# aircopter.net
KiCad netlist of a schematic drawn in EAGLE
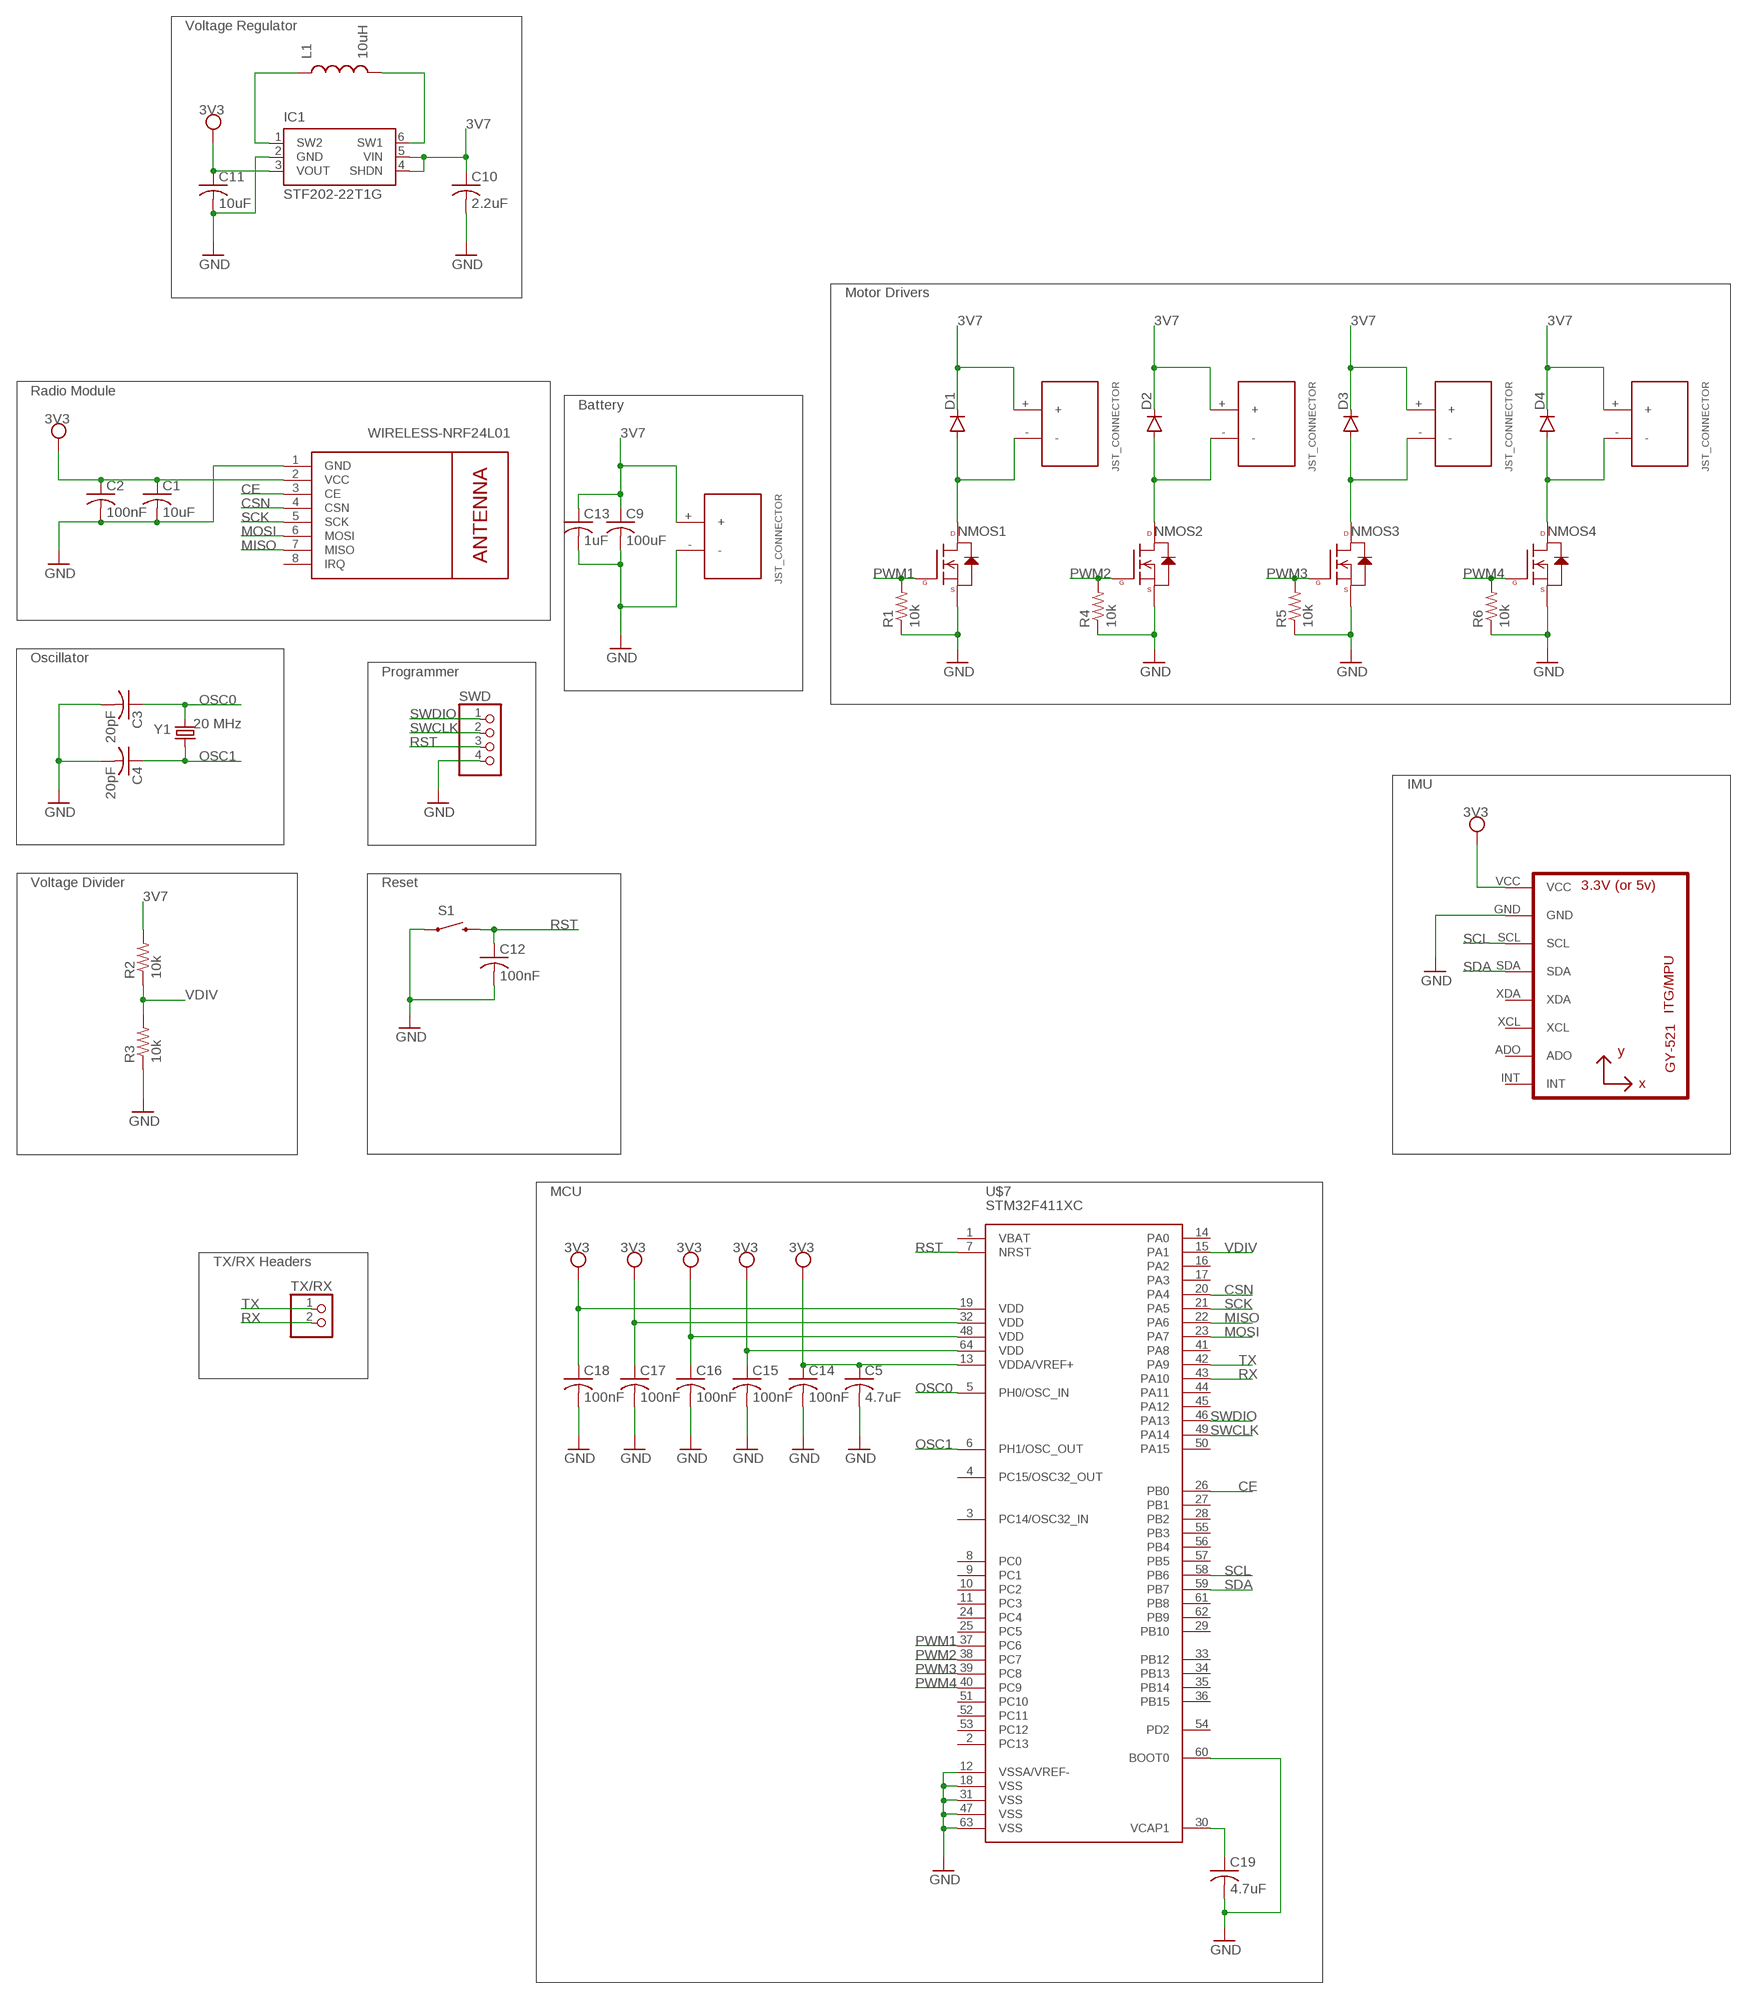
[diagram p0: schematic, sheet 1]

(export (version "E")
  (design (tool "Eeschema 10.0.6"))
  (components
    (comp (ref "C1")
      (value "10uF")
      (footprint "eagle-import:C0603")
      (libsource (lib "eagle-import") (part "C-USC0603"))
    )
    (comp (ref "C2")
      (value "100nF")
      (footprint "eagle-import:C0603")
      (libsource (lib "eagle-import") (part "C-USC0603"))
    )
    (comp (ref "C3")
      (value "20pF")
      (footprint "eagle-import:C0603")
      (libsource (lib "eagle-import") (part "C-USC0603"))
    )
    (comp (ref "C4")
      (value "20pF")
      (footprint "eagle-import:C0603")
      (libsource (lib "eagle-import") (part "C-USC0603"))
    )
    (comp (ref "C5")
      (value "4.7uF")
      (footprint "eagle-import:C0603")
      (libsource (lib "eagle-import") (part "C-USC0603"))
    )
    (comp (ref "C9")
      (value "100uF")
      (footprint "eagle-import:C0603")
      (libsource (lib "eagle-import") (part "C-USC0603"))
    )
    (comp (ref "C10")
      (value "2.2uF")
      (footprint "eagle-import:C0603")
      (libsource (lib "eagle-import") (part "C-USC0603"))
    )
    (comp (ref "C11")
      (value "10uF")
      (footprint "eagle-import:C0603")
      (libsource (lib "eagle-import") (part "C-USC0603"))
    )
    (comp (ref "C12")
      (value "100nF")
      (footprint "eagle-import:C0603")
      (libsource (lib "eagle-import") (part "C-USC0603"))
    )
    (comp (ref "C13")
      (value "1uF")
      (footprint "eagle-import:C0603")
      (libsource (lib "eagle-import") (part "C-USC0603"))
    )
    (comp (ref "C14")
      (value "100nF")
      (footprint "eagle-import:C0603")
      (libsource (lib "eagle-import") (part "C-USC0603"))
    )
    (comp (ref "C15")
      (value "100nF")
      (footprint "eagle-import:C0603")
      (libsource (lib "eagle-import") (part "C-USC0603"))
    )
    (comp (ref "C16")
      (value "100nF")
      (footprint "eagle-import:C0603")
      (libsource (lib "eagle-import") (part "C-USC0603"))
    )
    (comp (ref "C17")
      (value "100nF")
      (footprint "eagle-import:C0603")
      (libsource (lib "eagle-import") (part "C-USC0603"))
    )
    (comp (ref "C18")
      (value "100nF")
      (footprint "eagle-import:C0603")
      (libsource (lib "eagle-import") (part "C-USC0603"))
    )
    (comp (ref "C19")
      (value "4.7uF")
      (footprint "eagle-import:C0603")
      (libsource (lib "eagle-import") (part "C-USC0603"))
    )
    (comp (ref "D1")
      (value "DIODESMA")
      (footprint "eagle-import:SMA-DIODE")
      (libsource (lib "eagle-import") (part "DIODESMA"))
    )
    (comp (ref "D2")
      (value "DIODESMA")
      (footprint "eagle-import:SMA-DIODE")
      (libsource (lib "eagle-import") (part "DIODESMA"))
    )
    (comp (ref "D3")
      (value "DIODESMA")
      (footprint "eagle-import:SMA-DIODE")
      (libsource (lib "eagle-import") (part "DIODESMA"))
    )
    (comp (ref "D4")
      (value "DIODESMA")
      (footprint "eagle-import:SMA-DIODE")
      (libsource (lib "eagle-import") (part "DIODESMA"))
    )
    (comp (ref "IC1")
      (value "STF202-22T1G")
      (footprint "eagle-import:SOT23-6")
      (fields (field (name "MF") "ON Semiconductor"))
      (libsource (lib "eagle-import") (part "STF202-22T1G"))
    )
    (comp (ref "L1")
      (value "10uH")
      (footprint "eagle-import:L0603")
      (libsource (lib "eagle-import") (part "INDUCTOR"))
    )
    (comp (ref "M1")
      (value "WIRELESS-NRF24L01")
      (footprint "eagle-import:WIRELESS-NRF24L01")
      (libsource (lib "eagle-import") (part "WIRELESS-NRF24L01"))
    )
    (comp (ref "NMOS1")
      (value "N-CHANNEL-MOSFET-BSS138")
      (footprint "eagle-import:SOT23-3")
      (libsource (lib "eagle-import") (part "N-CHANNEL-MOSFET-BSS138"))
    )
    (comp (ref "NMOS2")
      (value "N-CHANNEL-MOSFET-BSS138")
      (footprint "eagle-import:SOT23-3")
      (libsource (lib "eagle-import") (part "N-CHANNEL-MOSFET-BSS138"))
    )
    (comp (ref "NMOS3")
      (value "N-CHANNEL-MOSFET-BSS138")
      (footprint "eagle-import:SOT23-3")
      (libsource (lib "eagle-import") (part "N-CHANNEL-MOSFET-BSS138"))
    )
    (comp (ref "NMOS4")
      (value "N-CHANNEL-MOSFET-BSS138")
      (footprint "eagle-import:SOT23-3")
      (libsource (lib "eagle-import") (part "N-CHANNEL-MOSFET-BSS138"))
    )
    (comp (ref "R1")
      (value "10k")
      (footprint "eagle-import:R0603")
      (libsource (lib "eagle-import") (part "R-US_R0603"))
    )
    (comp (ref "R2")
      (value "10k")
      (footprint "eagle-import:R0603")
      (libsource (lib "eagle-import") (part "R-US_R0603"))
    )
    (comp (ref "R3")
      (value "10k")
      (footprint "eagle-import:R0603")
      (libsource (lib "eagle-import") (part "R-US_R0603"))
    )
    (comp (ref "R4")
      (value "10k")
      (footprint "eagle-import:R0603")
      (libsource (lib "eagle-import") (part "R-US_R0603"))
    )
    (comp (ref "R5")
      (value "10k")
      (footprint "eagle-import:R0603")
      (libsource (lib "eagle-import") (part "R-US_R0603"))
    )
    (comp (ref "R6")
      (value "10k")
      (footprint "eagle-import:R0603")
      (libsource (lib "eagle-import") (part "R-US_R0603"))
    )
    (comp (ref "S1")
      (value "SWITCH-MOMENTARY-2SMD")
      (footprint "eagle-import:TACTILE-SWITCH-SMD")
      (libsource (lib "eagle-import") (part "SWITCH-MOMENTARY-2SMD"))
    )
    (comp (ref "SWD")
      (value "PINHD-1X4")
      (footprint "eagle-import:1X04")
      (libsource (lib "eagle-import") (part "PINHD-1X4"))
    )
    (comp (ref "TX/RX")
      (value "PINHD-1X2")
      (footprint "eagle-import:1X02")
      (libsource (lib "eagle-import") (part "PINHD-1X2"))
    )
    (comp (ref "U$2")
      (value "JST_CONNECTOR_FEMALE")
      (footprint "eagle-import:JST_CONNECTOR_FEMALE")
      (libsource (lib "eagle-import") (part "JST_CONNECTOR_FEMALE"))
    )
    (comp (ref "U$3")
      (value "JST_CONNECTOR_FEMALE")
      (footprint "eagle-import:JST_CONNECTOR_FEMALE")
      (libsource (lib "eagle-import") (part "JST_CONNECTOR_FEMALE"))
    )
    (comp (ref "U$4")
      (value "JST_CONNECTOR_FEMALE")
      (footprint "eagle-import:JST_CONNECTOR_FEMALE")
      (libsource (lib "eagle-import") (part "JST_CONNECTOR_FEMALE"))
    )
    (comp (ref "U$5")
      (value "JST_CONNECTOR_FEMALE")
      (footprint "eagle-import:JST_CONNECTOR_FEMALE")
      (libsource (lib "eagle-import") (part "JST_CONNECTOR_FEMALE"))
    )
    (comp (ref "U$6")
      (value "JST_CONNECTOR_FEMALE")
      (footprint "eagle-import:JST_CONNECTOR_FEMALE")
      (libsource (lib "eagle-import") (part "JST_CONNECTOR_FEMALE"))
    )
    (comp (ref "U$7")
      (value "STM32F411XC")
      (footprint "eagle-import:LQFP64")
      (libsource (lib "eagle-import") (part "STM32F411XC"))
    )
    (comp (ref "U2")
      (value "GY-521MPU6050")
      (footprint "eagle-import:GY-521")
      (libsource (lib "eagle-import") (part "GY-521MPU6050"))
    )
    (comp (ref "Y1")
      (value "20 MHz")
      (footprint "eagle-import:HC49UP")
      (libsource (lib "eagle-import") (part "CRYSTALSMD"))
    )
  )
  (nets
    (net (code "1") (name "/3V7") (class "Default")
      (node (ref "C10") (pin "1") (pinfunction "1_1") (pintype "passive"))
      (node (ref "C13") (pin "1") (pinfunction "1_1") (pintype "passive"))
      (node (ref "C9") (pin "1") (pinfunction "1_1") (pintype "passive"))
      (node (ref "D1") (pin "C") (pinfunction "C_C") (pintype "passive"))
      (node (ref "D2") (pin "C") (pinfunction "C_C") (pintype "passive"))
      (node (ref "D3") (pin "C") (pinfunction "C_C") (pintype "passive"))
      (node (ref "D4") (pin "C") (pinfunction "C_C") (pintype "passive"))
      (node (ref "IC1") (pin "4") (pinfunction "SHDN_4") (pintype "passive"))
      (node (ref "IC1") (pin "5") (pinfunction "VIN_5") (pintype "passive"))
      (node (ref "R2") (pin "2") (pinfunction "2_2") (pintype "passive"))
      (node (ref "U$2") (pin "+") (pinfunction "+_+") (pintype "bidirectional"))
      (node (ref "U$3") (pin "+") (pinfunction "+_+") (pintype "bidirectional"))
      (node (ref "U$4") (pin "+") (pinfunction "+_+") (pintype "bidirectional"))
      (node (ref "U$5") (pin "+") (pinfunction "+_+") (pintype "bidirectional"))
      (node (ref "U$6") (pin "+") (pinfunction "+_+") (pintype "bidirectional"))
    )
    (net (code "2") (name "/CE") (class "Default")
      (node (ref "M1") (pin "3") (pinfunction "CE_3") (pintype "bidirectional"))
      (node (ref "U$7") (pin "26") (pinfunction "PB0_26") (pintype "bidirectional"))
    )
    (net (code "3") (name "/CSN") (class "Default")
      (node (ref "M1") (pin "4") (pinfunction "CSN_4") (pintype "bidirectional"))
      (node (ref "U$7") (pin "20") (pinfunction "PA4_20") (pintype "bidirectional"))
    )
    (net (code "4") (name "/MISO") (class "Default")
      (node (ref "M1") (pin "7") (pinfunction "MISO_7") (pintype "bidirectional"))
      (node (ref "U$7") (pin "22") (pinfunction "PA6_22") (pintype "bidirectional"))
    )
    (net (code "5") (name "/MOSI") (class "Default")
      (node (ref "M1") (pin "6") (pinfunction "MOSI_6") (pintype "bidirectional"))
      (node (ref "U$7") (pin "23") (pinfunction "PA7_23") (pintype "bidirectional"))
    )
    (net (code "6") (name "/OSC0") (class "Default")
      (node (ref "C3") (pin "1") (pinfunction "1_1") (pintype "passive"))
      (node (ref "U$7") (pin "5") (pinfunction "PH0/OSC_IN_5") (pintype "bidirectional"))
      (node (ref "Y1") (pin "2") (pinfunction "2_2") (pintype "passive"))
    )
    (net (code "7") (name "/OSC1") (class "Default")
      (node (ref "C4") (pin "1") (pinfunction "1_1") (pintype "passive"))
      (node (ref "U$7") (pin "6") (pinfunction "PH1/OSC_OUT_6") (pintype "bidirectional"))
      (node (ref "Y1") (pin "1") (pinfunction "1_1") (pintype "passive"))
    )
    (net (code "8") (name "/PWM1") (class "Default")
      (node (ref "NMOS1") (pin "1") (pinfunction "G_1") (pintype "passive"))
      (node (ref "R1") (pin "2") (pinfunction "2_2") (pintype "passive"))
      (node (ref "U$7") (pin "37") (pinfunction "PC6_37") (pintype "bidirectional"))
    )
    (net (code "9") (name "/PWM2") (class "Default")
      (node (ref "NMOS2") (pin "1") (pinfunction "G_1") (pintype "passive"))
      (node (ref "R4") (pin "2") (pinfunction "2_2") (pintype "passive"))
      (node (ref "U$7") (pin "38") (pinfunction "PC7_38") (pintype "bidirectional"))
    )
    (net (code "10") (name "/PWM3") (class "Default")
      (node (ref "NMOS3") (pin "1") (pinfunction "G_1") (pintype "passive"))
      (node (ref "R5") (pin "2") (pinfunction "2_2") (pintype "passive"))
      (node (ref "U$7") (pin "39") (pinfunction "PC8_39") (pintype "bidirectional"))
    )
    (net (code "11") (name "/PWM4") (class "Default")
      (node (ref "NMOS4") (pin "1") (pinfunction "G_1") (pintype "passive"))
      (node (ref "R6") (pin "2") (pinfunction "2_2") (pintype "passive"))
      (node (ref "U$7") (pin "40") (pinfunction "PC9_40") (pintype "bidirectional"))
    )
    (net (code "12") (name "/RST") (class "Default")
      (node (ref "C12") (pin "1") (pinfunction "1_1") (pintype "passive"))
      (node (ref "S1") (pin "3") (pinfunction "2_3") (pintype "passive"))
      (node (ref "SWD") (pin "3") (pinfunction "3_3") (pintype "passive"))
      (node (ref "U$7") (pin "7") (pinfunction "NRST_7") (pintype "bidirectional"))
    )
    (net (code "13") (name "/RX") (class "Default")
      (node (ref "TX/RX") (pin "2") (pinfunction "2_2") (pintype "passive"))
      (node (ref "U$7") (pin "43") (pinfunction "PA10_43") (pintype "bidirectional"))
    )
    (net (code "14") (name "/SCK") (class "Default")
      (node (ref "M1") (pin "5") (pinfunction "SCK_5") (pintype "bidirectional"))
      (node (ref "U$7") (pin "21") (pinfunction "PA5_21") (pintype "bidirectional"))
    )
    (net (code "15") (name "/SCL") (class "Default")
      (node (ref "U$7") (pin "58") (pinfunction "PB6_58") (pintype "bidirectional"))
      (node (ref "U2") (pin "SCL") (pinfunction "SCL_SCL") (pintype "bidirectional"))
    )
    (net (code "16") (name "/SDA") (class "Default")
      (node (ref "U$7") (pin "59") (pinfunction "PB7_59") (pintype "bidirectional"))
      (node (ref "U2") (pin "SDA") (pinfunction "SDA_SDA") (pintype "bidirectional"))
    )
    (net (code "17") (name "/SWCLK") (class "Default")
      (node (ref "SWD") (pin "2") (pinfunction "2_2") (pintype "passive"))
      (node (ref "U$7") (pin "49") (pinfunction "PA14_49") (pintype "bidirectional"))
    )
    (net (code "18") (name "/SWDIO") (class "Default")
      (node (ref "SWD") (pin "1") (pinfunction "1_1") (pintype "passive"))
      (node (ref "U$7") (pin "46") (pinfunction "PA13_46") (pintype "bidirectional"))
    )
    (net (code "19") (name "/TX") (class "Default")
      (node (ref "TX/RX") (pin "1") (pinfunction "1_1") (pintype "passive"))
      (node (ref "U$7") (pin "42") (pinfunction "PA9_42") (pintype "bidirectional"))
    )
    (net (code "20") (name "/VDIV") (class "Default")
      (node (ref "R2") (pin "1") (pinfunction "1_1") (pintype "passive"))
      (node (ref "R3") (pin "2") (pinfunction "2_2") (pintype "passive"))
      (node (ref "U$7") (pin "15") (pinfunction "PA1_15") (pintype "bidirectional"))
    )
    (net (code "21") (name "3V3-CIRCLE") (class "Default")
      (node (ref "C1") (pin "1") (pinfunction "1_1") (pintype "passive"))
      (node (ref "C11") (pin "1") (pinfunction "1_1") (pintype "passive"))
      (node (ref "C14") (pin "1") (pinfunction "1_1") (pintype "passive"))
      (node (ref "C15") (pin "1") (pinfunction "1_1") (pintype "passive"))
      (node (ref "C16") (pin "1") (pinfunction "1_1") (pintype "passive"))
      (node (ref "C17") (pin "1") (pinfunction "1_1") (pintype "passive"))
      (node (ref "C18") (pin "1") (pinfunction "1_1") (pintype "passive"))
      (node (ref "C2") (pin "1") (pinfunction "1_1") (pintype "passive"))
      (node (ref "C5") (pin "1") (pinfunction "1_1") (pintype "passive"))
      (node (ref "IC1") (pin "3") (pinfunction "VOUT_3") (pintype "passive"))
      (node (ref "M1") (pin "2") (pinfunction "VCC_2") (pintype "power_in"))
      (node (ref "U$7") (pin "13") (pinfunction "VDDA/VREF+_13") (pintype "bidirectional"))
      (node (ref "U$7") (pin "19") (pinfunction "VDD_19") (pintype "bidirectional"))
      (node (ref "U$7") (pin "32") (pinfunction "VDD_32") (pintype "bidirectional"))
      (node (ref "U$7") (pin "48") (pinfunction "VDD_48") (pintype "bidirectional"))
      (node (ref "U$7") (pin "64") (pinfunction "VDD_64") (pintype "bidirectional"))
      (node (ref "U2") (pin "VCC") (pinfunction "VCC_VCC") (pintype "bidirectional"))
    )
    (net (code "22") (name "Net-(IC1-SW1)") (class "Default")
      (node (ref "IC1") (pin "6") (pinfunction "SW1_6") (pintype "passive"))
      (node (ref "L1") (pin "2") (pinfunction "2_2") (pintype "passive"))
    )
    (net (code "23") (name "Net-(IC1-SW2)") (class "Default")
      (node (ref "IC1") (pin "1") (pinfunction "SW2_1") (pintype "passive"))
      (node (ref "L1") (pin "1") (pinfunction "1_1") (pintype "passive"))
    )
    (net (code "24") (name "Net-(NMOS1-D)") (class "Default")
      (node (ref "D1") (pin "A") (pinfunction "A_A") (pintype "passive"))
      (node (ref "NMOS1") (pin "3") (pinfunction "D_3") (pintype "passive"))
      (node (ref "U$2") (pin "-") (pinfunction "-_-") (pintype "bidirectional"))
    )
    (net (code "25") (name "Net-(NMOS2-D)") (class "Default")
      (node (ref "D2") (pin "A") (pinfunction "A_A") (pintype "passive"))
      (node (ref "NMOS2") (pin "3") (pinfunction "D_3") (pintype "passive"))
      (node (ref "U$3") (pin "-") (pinfunction "-_-") (pintype "bidirectional"))
    )
    (net (code "26") (name "Net-(NMOS3-D)") (class "Default")
      (node (ref "D3") (pin "A") (pinfunction "A_A") (pintype "passive"))
      (node (ref "NMOS3") (pin "3") (pinfunction "D_3") (pintype "passive"))
      (node (ref "U$4") (pin "-") (pinfunction "-_-") (pintype "bidirectional"))
    )
    (net (code "27") (name "Net-(NMOS4-D)") (class "Default")
      (node (ref "D4") (pin "A") (pinfunction "A_A") (pintype "passive"))
      (node (ref "NMOS4") (pin "3") (pinfunction "D_3") (pintype "passive"))
      (node (ref "U$5") (pin "-") (pinfunction "-_-") (pintype "bidirectional"))
    )
    (net (code "28") (name "Net-(U$7-VCAP1)") (class "Default")
      (node (ref "C19") (pin "1") (pinfunction "1_1") (pintype "passive"))
      (node (ref "U$7") (pin "30") (pinfunction "VCAP1_30") (pintype "bidirectional"))
    )
    (net (code "29") (name "SUPPLY1_GND") (class "Default")
      (node (ref "C1") (pin "2") (pinfunction "2_2") (pintype "passive"))
      (node (ref "C10") (pin "2") (pinfunction "2_2") (pintype "passive"))
      (node (ref "C11") (pin "2") (pinfunction "2_2") (pintype "passive"))
      (node (ref "C12") (pin "2") (pinfunction "2_2") (pintype "passive"))
      (node (ref "C13") (pin "2") (pinfunction "2_2") (pintype "passive"))
      (node (ref "C14") (pin "2") (pinfunction "2_2") (pintype "passive"))
      (node (ref "C15") (pin "2") (pinfunction "2_2") (pintype "passive"))
      (node (ref "C16") (pin "2") (pinfunction "2_2") (pintype "passive"))
      (node (ref "C17") (pin "2") (pinfunction "2_2") (pintype "passive"))
      (node (ref "C18") (pin "2") (pinfunction "2_2") (pintype "passive"))
      (node (ref "C19") (pin "2") (pinfunction "2_2") (pintype "passive"))
      (node (ref "C2") (pin "2") (pinfunction "2_2") (pintype "passive"))
      (node (ref "C3") (pin "2") (pinfunction "2_2") (pintype "passive"))
      (node (ref "C4") (pin "2") (pinfunction "2_2") (pintype "passive"))
      (node (ref "C5") (pin "2") (pinfunction "2_2") (pintype "passive"))
      (node (ref "C9") (pin "2") (pinfunction "2_2") (pintype "passive"))
      (node (ref "IC1") (pin "2") (pinfunction "GND_2") (pintype "passive"))
      (node (ref "M1") (pin "1") (pinfunction "GND_1") (pintype "power_in"))
      (node (ref "NMOS1") (pin "2") (pinfunction "S_2") (pintype "passive"))
      (node (ref "NMOS2") (pin "2") (pinfunction "S_2") (pintype "passive"))
      (node (ref "NMOS3") (pin "2") (pinfunction "S_2") (pintype "passive"))
      (node (ref "NMOS4") (pin "2") (pinfunction "S_2") (pintype "passive"))
      (node (ref "R1") (pin "1") (pinfunction "1_1") (pintype "passive"))
      (node (ref "R3") (pin "1") (pinfunction "1_1") (pintype "passive"))
      (node (ref "R4") (pin "1") (pinfunction "1_1") (pintype "passive"))
      (node (ref "R5") (pin "1") (pinfunction "1_1") (pintype "passive"))
      (node (ref "R6") (pin "1") (pinfunction "1_1") (pintype "passive"))
      (node (ref "S1") (pin "1") (pinfunction "1_1") (pintype "passive"))
      (node (ref "SWD") (pin "4") (pinfunction "4_4") (pintype "passive"))
      (node (ref "U$6") (pin "-") (pinfunction "-_-") (pintype "bidirectional"))
      (node (ref "U$7") (pin "12") (pinfunction "VSSA/VREF-_12") (pintype "bidirectional"))
      (node (ref "U$7") (pin "18") (pinfunction "VSS_18") (pintype "bidirectional"))
      (node (ref "U$7") (pin "31") (pinfunction "VSS_31") (pintype "bidirectional"))
      (node (ref "U$7") (pin "47") (pinfunction "VSS_47") (pintype "bidirectional"))
      (node (ref "U$7") (pin "60") (pinfunction "BOOT0_60") (pintype "bidirectional"))
      (node (ref "U$7") (pin "63") (pinfunction "VSS_63") (pintype "bidirectional"))
      (node (ref "U2") (pin "GND") (pinfunction "GND_GND") (pintype "bidirectional"))
    )
    (net (code "30") (name "unconnected-(M1-IRQ-Pad8)") (class "Default")
      (node (ref "M1") (pin "8") (pinfunction "IRQ_8") (pintype "bidirectional"))
    )
    (net (code "31") (name "unconnected-(U$7-PA0-Pad14)") (class "Default")
      (node (ref "U$7") (pin "14") (pinfunction "PA0_14") (pintype "bidirectional"))
    )
    (net (code "32") (name "unconnected-(U$7-PA2-Pad16)") (class "Default")
      (node (ref "U$7") (pin "16") (pinfunction "PA2_16") (pintype "bidirectional"))
    )
    (net (code "33") (name "unconnected-(U$7-PA3-Pad17)") (class "Default")
      (node (ref "U$7") (pin "17") (pinfunction "PA3_17") (pintype "bidirectional"))
    )
    (net (code "34") (name "unconnected-(U$7-PA8-Pad41)") (class "Default")
      (node (ref "U$7") (pin "41") (pinfunction "PA8_41") (pintype "bidirectional"))
    )
    (net (code "35") (name "unconnected-(U$7-PA11-Pad44)") (class "Default")
      (node (ref "U$7") (pin "44") (pinfunction "PA11_44") (pintype "bidirectional"))
    )
    (net (code "36") (name "unconnected-(U$7-PA12-Pad45)") (class "Default")
      (node (ref "U$7") (pin "45") (pinfunction "PA12_45") (pintype "bidirectional"))
    )
    (net (code "37") (name "unconnected-(U$7-PA15-Pad50)") (class "Default")
      (node (ref "U$7") (pin "50") (pinfunction "PA15_50") (pintype "bidirectional"))
    )
    (net (code "38") (name "unconnected-(U$7-PB1-Pad27)") (class "Default")
      (node (ref "U$7") (pin "27") (pinfunction "PB1_27") (pintype "bidirectional"))
    )
    (net (code "39") (name "unconnected-(U$7-PB2-Pad28)") (class "Default")
      (node (ref "U$7") (pin "28") (pinfunction "PB2_28") (pintype "bidirectional"))
    )
    (net (code "40") (name "unconnected-(U$7-PB3-Pad55)") (class "Default")
      (node (ref "U$7") (pin "55") (pinfunction "PB3_55") (pintype "bidirectional"))
    )
    (net (code "41") (name "unconnected-(U$7-PB4-Pad56)") (class "Default")
      (node (ref "U$7") (pin "56") (pinfunction "PB4_56") (pintype "bidirectional"))
    )
    (net (code "42") (name "unconnected-(U$7-PB5-Pad57)") (class "Default")
      (node (ref "U$7") (pin "57") (pinfunction "PB5_57") (pintype "bidirectional"))
    )
    (net (code "43") (name "unconnected-(U$7-PB8-Pad61)") (class "Default")
      (node (ref "U$7") (pin "61") (pinfunction "PB8_61") (pintype "bidirectional"))
    )
    (net (code "44") (name "unconnected-(U$7-PB9-Pad62)") (class "Default")
      (node (ref "U$7") (pin "62") (pinfunction "PB9_62") (pintype "bidirectional"))
    )
    (net (code "45") (name "unconnected-(U$7-PB10-Pad29)") (class "Default")
      (node (ref "U$7") (pin "29") (pinfunction "PB10_29") (pintype "bidirectional"))
    )
    (net (code "46") (name "unconnected-(U$7-PB12-Pad33)") (class "Default")
      (node (ref "U$7") (pin "33") (pinfunction "PB12_33") (pintype "bidirectional"))
    )
    (net (code "47") (name "unconnected-(U$7-PB13-Pad34)") (class "Default")
      (node (ref "U$7") (pin "34") (pinfunction "PB13_34") (pintype "bidirectional"))
    )
    (net (code "48") (name "unconnected-(U$7-PB14-Pad35)") (class "Default")
      (node (ref "U$7") (pin "35") (pinfunction "PB14_35") (pintype "bidirectional"))
    )
    (net (code "49") (name "unconnected-(U$7-PB15-Pad36)") (class "Default")
      (node (ref "U$7") (pin "36") (pinfunction "PB15_36") (pintype "bidirectional"))
    )
    (net (code "50") (name "unconnected-(U$7-PC0-Pad8)") (class "Default")
      (node (ref "U$7") (pin "8") (pinfunction "PC0_8") (pintype "bidirectional"))
    )
    (net (code "51") (name "unconnected-(U$7-PC1-Pad9)") (class "Default")
      (node (ref "U$7") (pin "9") (pinfunction "PC1_9") (pintype "bidirectional"))
    )
    (net (code "52") (name "unconnected-(U$7-PC2-Pad10)") (class "Default")
      (node (ref "U$7") (pin "10") (pinfunction "PC2_10") (pintype "bidirectional"))
    )
    (net (code "53") (name "unconnected-(U$7-PC3-Pad11)") (class "Default")
      (node (ref "U$7") (pin "11") (pinfunction "PC3_11") (pintype "bidirectional"))
    )
    (net (code "54") (name "unconnected-(U$7-PC4-Pad24)") (class "Default")
      (node (ref "U$7") (pin "24") (pinfunction "PC4_24") (pintype "bidirectional"))
    )
    (net (code "55") (name "unconnected-(U$7-PC5-Pad25)") (class "Default")
      (node (ref "U$7") (pin "25") (pinfunction "PC5_25") (pintype "bidirectional"))
    )
    (net (code "56") (name "unconnected-(U$7-PC10-Pad51)") (class "Default")
      (node (ref "U$7") (pin "51") (pinfunction "PC10_51") (pintype "bidirectional"))
    )
    (net (code "57") (name "unconnected-(U$7-PC11-Pad52)") (class "Default")
      (node (ref "U$7") (pin "52") (pinfunction "PC11_52") (pintype "bidirectional"))
    )
    (net (code "58") (name "unconnected-(U$7-PC12-Pad53)") (class "Default")
      (node (ref "U$7") (pin "53") (pinfunction "PC12_53") (pintype "bidirectional"))
    )
    (net (code "59") (name "unconnected-(U$7-PC13-Pad2)") (class "Default")
      (node (ref "U$7") (pin "2") (pinfunction "PC13_2") (pintype "bidirectional"))
    )
    (net (code "60") (name "unconnected-(U$7-PC14{slash}OSC32_IN-Pad3)") (class "Default")
      (node (ref "U$7") (pin "3") (pinfunction "PC14/OSC32_IN_3") (pintype "bidirectional"))
    )
    (net (code "61") (name "unconnected-(U$7-PC15{slash}OSC32_OUT-Pad4)") (class "Default")
      (node (ref "U$7") (pin "4") (pinfunction "PC15/OSC32_OUT_4") (pintype "bidirectional"))
    )
    (net (code "62") (name "unconnected-(U$7-PD2-Pad54)") (class "Default")
      (node (ref "U$7") (pin "54") (pinfunction "PD2_54") (pintype "bidirectional"))
    )
    (net (code "63") (name "unconnected-(U$7-VBAT-Pad1)") (class "Default")
      (node (ref "U$7") (pin "1") (pinfunction "VBAT_1") (pintype "bidirectional"))
    )
    (net (code "64") (name "unconnected-(U2-PadADO)") (class "Default")
      (node (ref "U2") (pin "ADO") (pinfunction "ADO_ADO") (pintype "bidirectional"))
    )
    (net (code "65") (name "unconnected-(U2-PadINT)") (class "Default")
      (node (ref "U2") (pin "INT") (pinfunction "INT_INT") (pintype "bidirectional"))
    )
    (net (code "66") (name "unconnected-(U2-PadXCL)") (class "Default")
      (node (ref "U2") (pin "XCL") (pinfunction "XCL_XCL") (pintype "bidirectional"))
    )
    (net (code "67") (name "unconnected-(U2-PadXDA)") (class "Default")
      (node (ref "U2") (pin "XDA") (pinfunction "XDA_XDA") (pintype "bidirectional"))
    )
  )
)
